# ATWork2022.net
KiCad netlist of a schematic drawn in Altium Designer
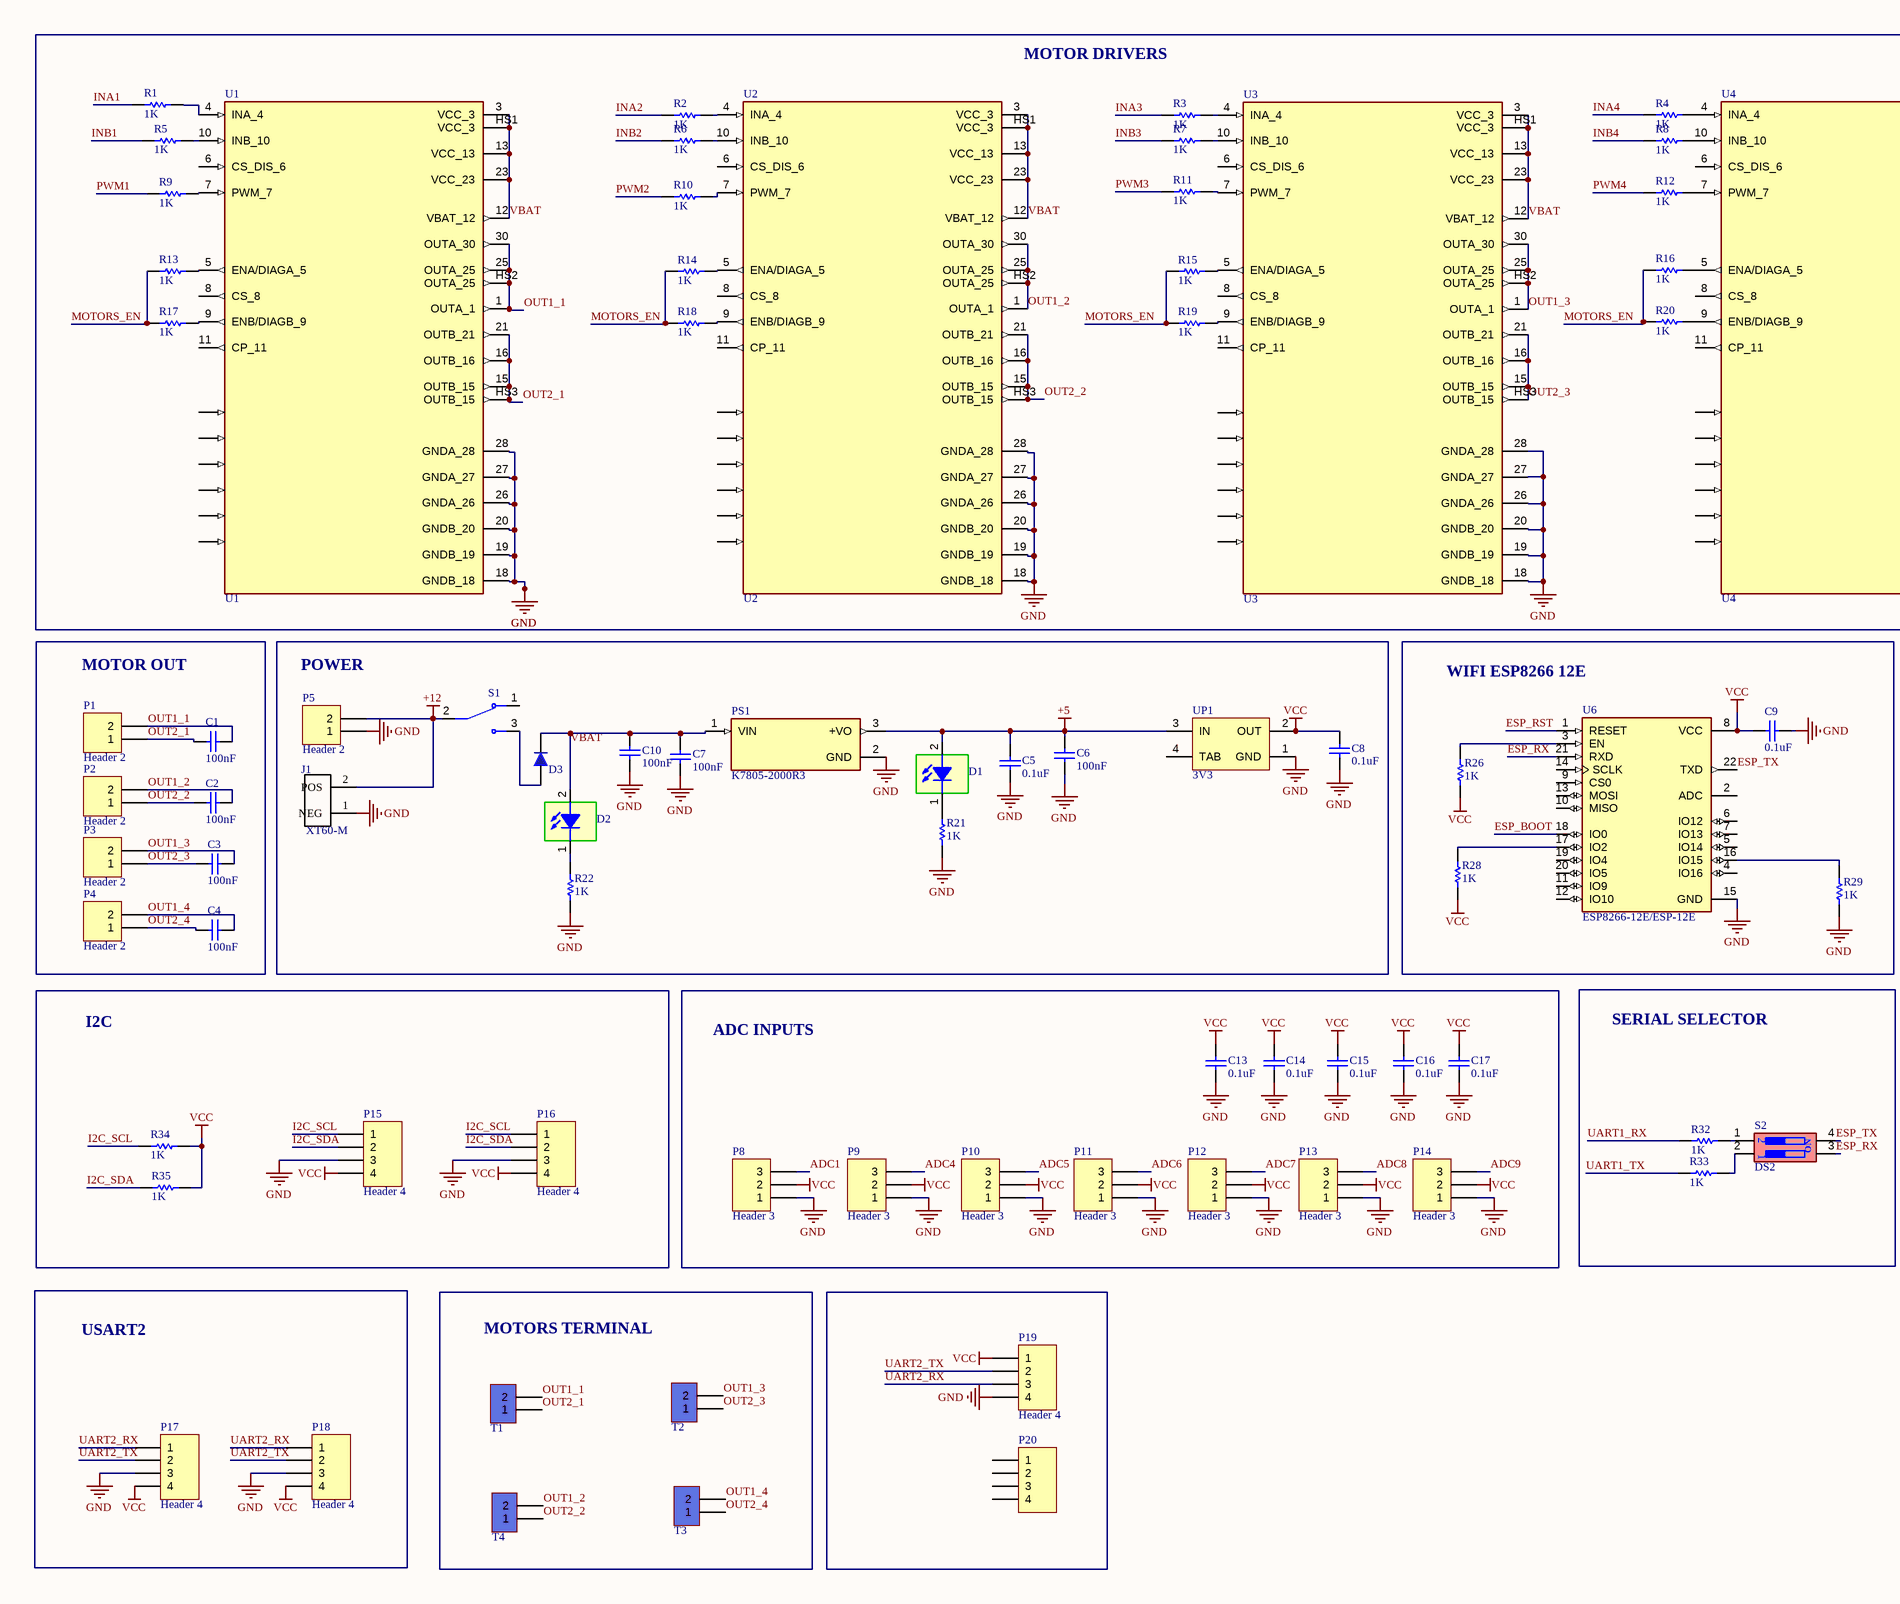
[diagram p0: ATWork2022.SchDoc, left]
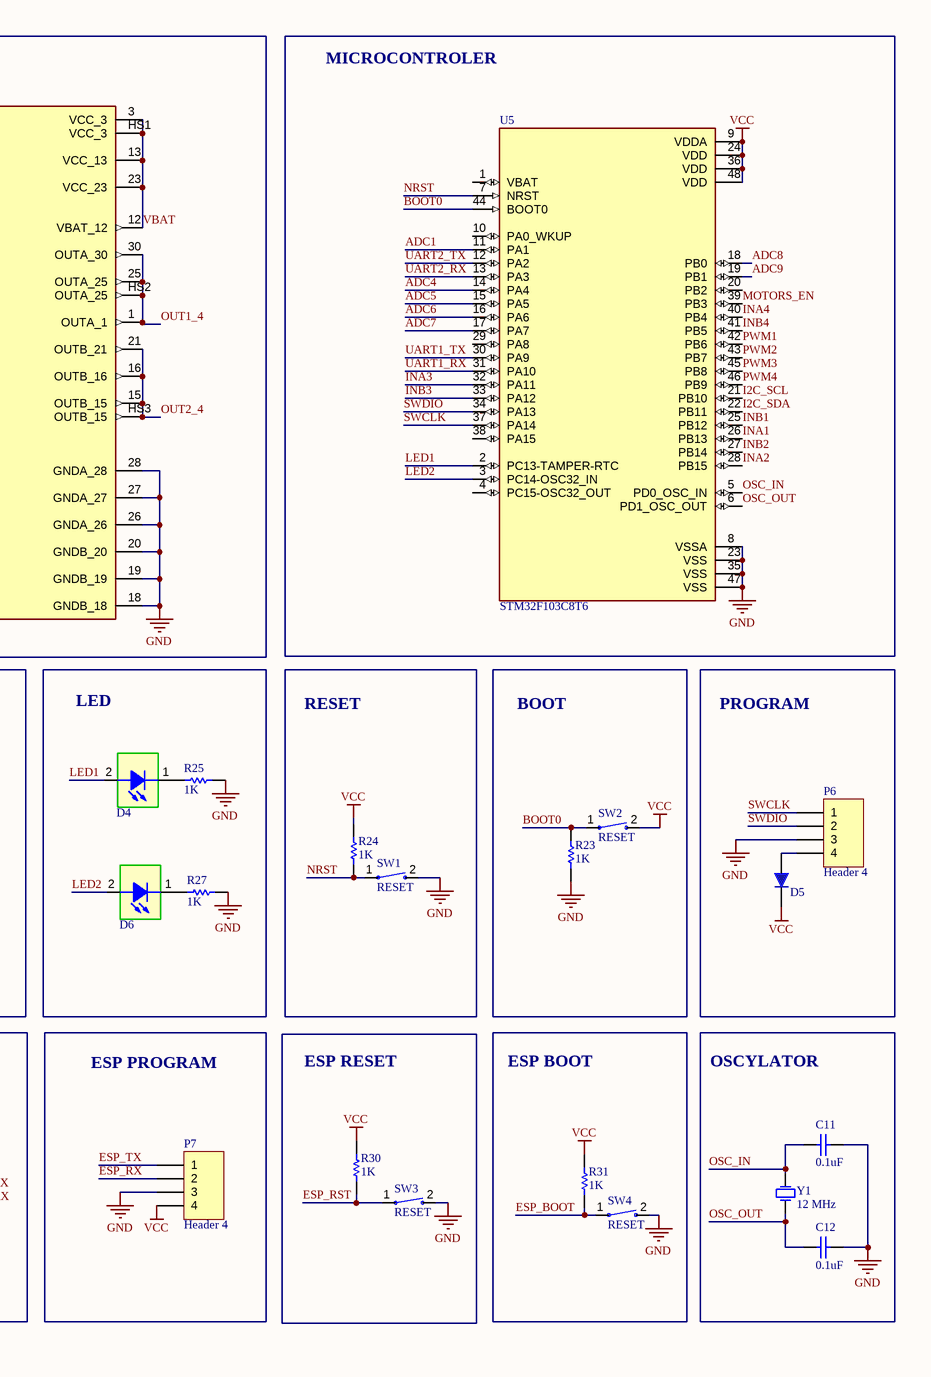
[diagram p1: ATWork2022.SchDoc, right]

(export (version "E")
  (design (tool "Eeschema 10.0.6"))
  (components
    (comp (ref "C1")
      (value "100nF")
      (footprint "CAPC4817X12N")
      (description "CAP 1206")
      (fields (field (name "DESIGNER") "Abbas Basereh"))
      (libsource (lib "Altium") (part "CAP SMD 1206"))
    )
    (comp (ref "C2")
      (value "100nF")
      (footprint "CAPC4817X12N")
      (description "CAP 1206")
      (fields (field (name "DESIGNER") "Abbas Basereh"))
      (libsource (lib "Altium") (part "CAP SMD 1206"))
    )
    (comp (ref "C3")
      (value "100nF")
      (footprint "CAPC4817X12N")
      (description "CAP 1206")
      (fields (field (name "DESIGNER") "Abbas Basereh"))
      (libsource (lib "Altium") (part "CAP SMD 1206"))
    )
    (comp (ref "C4")
      (value "100nF")
      (footprint "CAPC4817X12N")
      (description "CAP 1206")
      (fields (field (name "DESIGNER") "Abbas Basereh"))
      (libsource (lib "Altium") (part "CAP SMD 1206"))
    )
    (comp (ref "C5")
      (value "0.1uF")
      (footprint "CAPC4817X12N")
      (description "CAP 1206")
      (fields (field (name "DESIGNER") "Abbas Basereh"))
      (libsource (lib "Altium") (part "CAP SMD 1206"))
    )
    (comp (ref "C6")
      (value "100nF")
      (footprint "Cap SMD 100UF 35~50v")
      (description "TOTAL CAPACITOR SMD PACK")
      (fields (field (name "DESIGNER") "Abbas Basereh"))
      (libsource (lib "Altium") (part "CAP SMD PACKAGE"))
    )
    (comp (ref "C7")
      (value "100nF")
      (footprint "Cap SMD 100UF 35~50v")
      (description "TOTAL CAPACITOR SMD PACK")
      (fields (field (name "DESIGNER") "Abbas Basereh"))
      (libsource (lib "Altium") (part "CAP SMD PACKAGE"))
    )
    (comp (ref "C8")
      (value "0.1uF")
      (footprint "CAPC4817X12N")
      (description "CAP 1206")
      (fields (field (name "DESIGNER") "Abbas Basereh"))
      (libsource (lib "Altium") (part "CAP SMD 1206"))
    )
    (comp (ref "C9")
      (value "0.1uF")
      (footprint "CAPC4817X12N")
      (description "CAP 1206")
      (fields (field (name "DESIGNER") "Abbas Basereh"))
      (libsource (lib "Altium") (part "CAP SMD 1206"))
    )
    (comp (ref "C10")
      (value "100nF")
      (footprint "Cap SMD 100UF 35~50v")
      (description "TOTAL CAPACITOR SMD PACK")
      (fields (field (name "DESIGNER") "Abbas Basereh"))
      (libsource (lib "Altium") (part "CAP SMD PACKAGE"))
    )
    (comp (ref "C11")
      (value "0.1uF")
      (footprint "CAPC4817X12N")
      (description "CAP 1206")
      (fields (field (name "DESIGNER") "Abbas Basereh"))
      (libsource (lib "Altium") (part "CAP SMD 1206"))
    )
    (comp (ref "C12")
      (value "0.1uF")
      (footprint "CAPC4817X12N")
      (description "CAP 1206")
      (fields (field (name "DESIGNER") "Abbas Basereh"))
      (libsource (lib "Altium") (part "CAP SMD 1206"))
    )
    (comp (ref "C13")
      (value "0.1uF")
      (footprint "CAPC4817X12N")
      (description "CAP 1206")
      (fields (field (name "DESIGNER") "Abbas Basereh"))
      (libsource (lib "Altium") (part "CAP SMD 1206"))
    )
    (comp (ref "C14")
      (value "0.1uF")
      (footprint "CAPC4817X12N")
      (description "CAP 1206")
      (fields (field (name "DESIGNER") "Abbas Basereh"))
      (libsource (lib "Altium") (part "CAP SMD 1206"))
    )
    (comp (ref "C15")
      (value "0.1uF")
      (footprint "CAPC4817X12N")
      (description "CAP 1206")
      (fields (field (name "DESIGNER") "Abbas Basereh"))
      (libsource (lib "Altium") (part "CAP SMD 1206"))
    )
    (comp (ref "C16")
      (value "0.1uF")
      (footprint "CAPC4817X12N")
      (description "CAP 1206")
      (fields (field (name "DESIGNER") "Abbas Basereh"))
      (libsource (lib "Altium") (part "CAP SMD 1206"))
    )
    (comp (ref "C17")
      (value "0.1uF")
      (footprint "CAPC4817X12N")
      (description "CAP 1206")
      (fields (field (name "DESIGNER") "Abbas Basereh"))
      (libsource (lib "Altium") (part "CAP SMD 1206"))
    )
    (comp (ref "D1")
      (value "SMD 1206 LED")
      (footprint "LED 1206")
      (libsource (lib "") (part "LED SMD 1206_1"))
    )
    (comp (ref "D2")
      (value "SMD 1206 LED")
      (footprint "LED 1206")
      (libsource (lib "") (part "LED SMD 1206_1"))
    )
    (comp (ref "D3")
      (value "1n4007")
      (footprint "DIOM4629X24N")
      (description "Standard Rectifiers")
      (fields (field (name "MANUFACTURER") "DC COMPONENTS") (field (name "DESIGNER") "Abbas Basereh"))
      (libsource (lib "Altium") (part "1n4007 SMD M7"))
    )
    (comp (ref "D4")
      (value "SMD 1206 LED")
      (footprint "LED 1206")
      (libsource (lib "Altium") (part "LED SMD 1206"))
    )
    (comp (ref "D5")
      (value "1n4007")
      (footprint "DIOM4629X24N")
      (description "Standard Rectifiers")
      (fields (field (name "MANUFACTURER") "DC COMPONENTS") (field (name "DESIGNER") "Abbas Basereh"))
      (libsource (lib "Altium") (part "1n4007 SMD M7"))
    )
    (comp (ref "D6")
      (value "SMD 1206 LED")
      (footprint "LED 1206")
      (libsource (lib "Altium") (part "LED SMD 1206"))
    )
    (comp (ref "J1")
      (value "XT60-M")
      (footprint "*AMASS_XT60-M")
      (description "Plug; DC supply; XT60; male; PIN: 2; for cable; soldered; 30A; 500V")
      (fields (field (name "MF") "AMASS"))
      (libsource (lib "XT60-M") (part "XT60-M"))
    )
    (comp (ref "P1")
      (value "Header 2")
      (footprint "HDR1X2")
      (description "Header, 2-Pin")
      (fields (field (name "PUBLISHER") "Altium Limited"))
      (libsource (lib "Altium") (part "Header 2"))
    )
    (comp (ref "P2")
      (value "Header 2")
      (footprint "HDR1X2")
      (description "Header, 2-Pin")
      (fields (field (name "PUBLISHER") "Altium Limited"))
      (libsource (lib "Altium") (part "Header 2"))
    )
    (comp (ref "P3")
      (value "Header 2")
      (footprint "HDR1X2")
      (description "Header, 2-Pin")
      (fields (field (name "PUBLISHER") "Altium Limited"))
      (libsource (lib "Altium") (part "Header 2"))
    )
    (comp (ref "P4")
      (value "Header 2")
      (footprint "HDR1X2")
      (description "Header, 2-Pin")
      (fields (field (name "PUBLISHER") "Altium Limited"))
      (libsource (lib "Altium") (part "Header 2"))
    )
    (comp (ref "P5")
      (value "Header 2")
      (footprint "HDR1X2")
      (description "Header, 2-Pin")
      (fields (field (name "PUBLISHER") "Altium Limited"))
      (libsource (lib "Altium") (part "Header 2"))
    )
    (comp (ref "P6")
      (value "Header 4")
      (footprint "HDR1X4")
      (description "Header, 4-Pin")
      (fields (field (name "PUBLISHER") "Altium Limited"))
      (libsource (lib "Altium") (part "Header 4"))
    )
    (comp (ref "P7")
      (value "Header 4")
      (footprint "HDR1X4")
      (description "Header, 4-Pin")
      (fields (field (name "PUBLISHER") "Altium Limited"))
      (libsource (lib "Altium") (part "Header 4"))
    )
    (comp (ref "P8")
      (value "Header 3")
      (footprint "HDR1X3")
      (description "Header, 3-Pin")
      (fields (field (name "PUBLISHER") "Altium Limited"))
      (libsource (lib "Altium") (part "Header 3"))
    )
    (comp (ref "P9")
      (value "Header 3")
      (footprint "HDR1X3")
      (description "Header, 3-Pin")
      (fields (field (name "PUBLISHER") "Altium Limited"))
      (libsource (lib "Altium") (part "Header 3"))
    )
    (comp (ref "P10")
      (value "Header 3")
      (footprint "HDR1X3")
      (description "Header, 3-Pin")
      (fields (field (name "PUBLISHER") "Altium Limited"))
      (libsource (lib "Altium") (part "Header 3"))
    )
    (comp (ref "P11")
      (value "Header 3")
      (footprint "HDR1X3")
      (description "Header, 3-Pin")
      (fields (field (name "PUBLISHER") "Altium Limited"))
      (libsource (lib "Altium") (part "Header 3"))
    )
    (comp (ref "P12")
      (value "Header 3")
      (footprint "HDR1X3")
      (description "Header, 3-Pin")
      (fields (field (name "PUBLISHER") "Altium Limited"))
      (libsource (lib "Altium") (part "Header 3"))
    )
    (comp (ref "P13")
      (value "Header 3")
      (footprint "HDR1X3")
      (description "Header, 3-Pin")
      (fields (field (name "PUBLISHER") "Altium Limited"))
      (libsource (lib "Altium") (part "Header 3"))
    )
    (comp (ref "P14")
      (value "Header 3")
      (footprint "HDR1X3")
      (description "Header, 3-Pin")
      (fields (field (name "PUBLISHER") "Altium Limited"))
      (libsource (lib "Altium") (part "Header 3"))
    )
    (comp (ref "P15")
      (value "Header 4")
      (footprint "HDR1X4")
      (description "Header, 4-Pin")
      (fields (field (name "PUBLISHER") "Altium Limited"))
      (libsource (lib "Altium") (part "Header 4"))
    )
    (comp (ref "P16")
      (value "Header 4")
      (footprint "HDR1X4")
      (description "Header, 4-Pin")
      (fields (field (name "PUBLISHER") "Altium Limited"))
      (libsource (lib "Altium") (part "Header 4"))
    )
    (comp (ref "P17")
      (value "Header 4")
      (footprint "HDR1X4")
      (description "Header, 4-Pin")
      (fields (field (name "PUBLISHER") "Altium Limited"))
      (libsource (lib "Altium") (part "Header 4"))
    )
    (comp (ref "P18")
      (value "Header 4")
      (footprint "HDR1X4")
      (description "Header, 4-Pin")
      (fields (field (name "PUBLISHER") "Altium Limited"))
      (libsource (lib "Altium") (part "Header 4"))
    )
    (comp (ref "P19")
      (value "Header 4")
      (footprint "HDR1X4")
      (description "Header, 4-Pin")
      (fields (field (name "PUBLISHER") "Altium Limited"))
      (libsource (lib "Altium") (part "Header 4"))
    )
    (comp (ref "P20")
      (value "Header 4")
      (footprint "My_1X04")
      (description "Header, 4-Pin")
      (fields (field (name "PUBLISHER") "Altium Limited"))
      (libsource (lib "AMINLIB") (part "Header 4"))
    )
    (comp (ref "PS1")
      (value "K7805-2000R3")
      (footprint "CONV_K7805-2000R3")
      (description "éžçµ¶ç¸åž‹ PoL ãƒ¢ã‚¸ãƒ¥ãƒ¼ãƒ« DC DC ã‚³ãƒ³ãƒãƒ¼ã‚¿ 1 å‡ºåŠ› 5V 2A 8V - 36V å…¥åŠ›")
      (fields
        (field (name "MF") "Mornsun America, LLC")
        (field (name "DIGI-KEY_PART_NUMBER") "2725-K7805-2000R3-ND")
      )
      (libsource (lib "K7805-2000R3") (part "K7805-2000R3"))
    )
    (comp (ref "R1")
      (value "1K")
      (footprint "RESC3413X04N")
      (description "RES 0805")
      (fields (field (name "DESIGNER") "Abbas Basereh"))
      (libsource (lib "Altium") (part "RES 0805 0.125W"))
    )
    (comp (ref "R2")
      (value "1K")
      (footprint "RESC3413X04N")
      (description "RES 0805")
      (fields (field (name "DESIGNER") "Abbas Basereh"))
      (libsource (lib "Altium") (part "RES 0805 0.125W"))
    )
    (comp (ref "R3")
      (value "1K")
      (footprint "RESC3413X04N")
      (description "RES 0805")
      (fields (field (name "DESIGNER") "Abbas Basereh"))
      (libsource (lib "Altium") (part "RES 0805 0.125W"))
    )
    (comp (ref "R4")
      (value "1K")
      (footprint "RESC3413X04N")
      (description "RES 0805")
      (fields (field (name "DESIGNER") "Abbas Basereh"))
      (libsource (lib "Altium") (part "RES 0805 0.125W"))
    )
    (comp (ref "R5")
      (value "1K")
      (footprint "RESC3413X04N")
      (description "RES 0805")
      (fields (field (name "DESIGNER") "Abbas Basereh"))
      (libsource (lib "Altium") (part "RES 0805 0.125W"))
    )
    (comp (ref "R6")
      (value "1K")
      (footprint "RESC3413X04N")
      (description "RES 0805")
      (fields (field (name "DESIGNER") "Abbas Basereh"))
      (libsource (lib "Altium") (part "RES 0805 0.125W"))
    )
    (comp (ref "R7")
      (value "1K")
      (footprint "RESC3413X04N")
      (description "RES 0805")
      (fields (field (name "DESIGNER") "Abbas Basereh"))
      (libsource (lib "Altium") (part "RES 0805 0.125W"))
    )
    (comp (ref "R8")
      (value "1K")
      (footprint "RESC3413X04N")
      (description "RES 0805")
      (fields (field (name "DESIGNER") "Abbas Basereh"))
      (libsource (lib "Altium") (part "RES 0805 0.125W"))
    )
    (comp (ref "R9")
      (value "1K")
      (footprint "RESC3413X04N")
      (description "RES 0805")
      (fields (field (name "DESIGNER") "Abbas Basereh"))
      (libsource (lib "Altium") (part "RES 0805 0.125W"))
    )
    (comp (ref "R10")
      (value "1K")
      (footprint "RESC3413X04N")
      (description "RES 0805")
      (fields (field (name "DESIGNER") "Abbas Basereh"))
      (libsource (lib "Altium") (part "RES 0805 0.125W"))
    )
    (comp (ref "R11")
      (value "1K")
      (footprint "RESC3413X04N")
      (description "RES 0805")
      (fields (field (name "DESIGNER") "Abbas Basereh"))
      (libsource (lib "Altium") (part "RES 0805 0.125W"))
    )
    (comp (ref "R12")
      (value "1K")
      (footprint "RESC3413X04N")
      (description "RES 0805")
      (fields (field (name "DESIGNER") "Abbas Basereh"))
      (libsource (lib "Altium") (part "RES 0805 0.125W"))
    )
    (comp (ref "R13")
      (value "1K")
      (footprint "RESC3413X04N")
      (description "RES 0805")
      (fields (field (name "DESIGNER") "Abbas Basereh"))
      (libsource (lib "Altium") (part "RES 0805 0.125W"))
    )
    (comp (ref "R14")
      (value "1K")
      (footprint "RESC3413X04N")
      (description "RES 0805")
      (fields (field (name "DESIGNER") "Abbas Basereh"))
      (libsource (lib "Altium") (part "RES 0805 0.125W"))
    )
    (comp (ref "R15")
      (value "1K")
      (footprint "RESC3413X04N")
      (description "RES 0805")
      (fields (field (name "DESIGNER") "Abbas Basereh"))
      (libsource (lib "Altium") (part "RES 0805 0.125W"))
    )
    (comp (ref "R16")
      (value "1K")
      (footprint "RESC3413X04N")
      (description "RES 0805")
      (fields (field (name "DESIGNER") "Abbas Basereh"))
      (libsource (lib "Altium") (part "RES 0805 0.125W"))
    )
    (comp (ref "R17")
      (value "1K")
      (footprint "RESC3413X04N")
      (description "RES 0805")
      (fields (field (name "DESIGNER") "Abbas Basereh"))
      (libsource (lib "Altium") (part "RES 0805 0.125W"))
    )
    (comp (ref "R18")
      (value "1K")
      (footprint "RESC3413X04N")
      (description "RES 0805")
      (fields (field (name "DESIGNER") "Abbas Basereh"))
      (libsource (lib "Altium") (part "RES 0805 0.125W"))
    )
    (comp (ref "R19")
      (value "1K")
      (footprint "RESC3413X04N")
      (description "RES 0805")
      (fields (field (name "DESIGNER") "Abbas Basereh"))
      (libsource (lib "Altium") (part "RES 0805 0.125W"))
    )
    (comp (ref "R20")
      (value "1K")
      (footprint "RESC3413X04N")
      (description "RES 0805")
      (fields (field (name "DESIGNER") "Abbas Basereh"))
      (libsource (lib "Altium") (part "RES 0805 0.125W"))
    )
    (comp (ref "R21")
      (value "1K")
      (footprint "RESC3413X04N")
      (description "RES 0805")
      (fields (field (name "DESIGNER") "Abbas Basereh"))
      (libsource (lib "Altium") (part "RES 0805 0.125W"))
    )
    (comp (ref "R22")
      (value "1K")
      (footprint "RESC3413X04N")
      (description "RES 0805")
      (fields (field (name "DESIGNER") "Abbas Basereh"))
      (libsource (lib "Altium") (part "RES 0805 0.125W"))
    )
    (comp (ref "R23")
      (value "1K")
      (footprint "RESC3413X04N")
      (description "RES 0805")
      (fields (field (name "DESIGNER") "Abbas Basereh"))
      (libsource (lib "Altium") (part "RES 0805 0.125W"))
    )
    (comp (ref "R24")
      (value "1K")
      (footprint "RESC3413X04N")
      (description "RES 0805")
      (fields (field (name "DESIGNER") "Abbas Basereh"))
      (libsource (lib "Altium") (part "RES 0805 0.125W"))
    )
    (comp (ref "R25")
      (value "1K")
      (footprint "RESC3413X04N")
      (description "RES 0805")
      (fields (field (name "DESIGNER") "Abbas Basereh"))
      (libsource (lib "Altium") (part "RES 0805 0.125W"))
    )
    (comp (ref "R26")
      (value "1K")
      (footprint "RESC3413X04N")
      (description "RES 0805")
      (fields (field (name "DESIGNER") "Abbas Basereh"))
      (libsource (lib "Altium") (part "RES 0805 0.125W"))
    )
    (comp (ref "R27")
      (value "1K")
      (footprint "RESC3413X04N")
      (description "RES 0805")
      (fields (field (name "DESIGNER") "Abbas Basereh"))
      (libsource (lib "Altium") (part "RES 0805 0.125W"))
    )
    (comp (ref "R28")
      (value "1K")
      (footprint "RESC3413X04N")
      (description "RES 0805")
      (fields (field (name "DESIGNER") "Abbas Basereh"))
      (libsource (lib "Altium") (part "RES 0805 0.125W"))
    )
    (comp (ref "R29")
      (value "1K")
      (footprint "RESC3413X04N")
      (description "RES 0805")
      (fields (field (name "DESIGNER") "Abbas Basereh"))
      (libsource (lib "Altium") (part "RES 0805 0.125W"))
    )
    (comp (ref "R30")
      (value "1K")
      (footprint "RESC3413X04N")
      (description "RES 0805")
      (fields (field (name "DESIGNER") "Abbas Basereh"))
      (libsource (lib "Altium") (part "RES 0805 0.125W"))
    )
    (comp (ref "R31")
      (value "1K")
      (footprint "RESC3413X04N")
      (description "RES 0805")
      (fields (field (name "DESIGNER") "Abbas Basereh"))
      (libsource (lib "Altium") (part "RES 0805 0.125W"))
    )
    (comp (ref "R32")
      (value "1K")
      (footprint "RESC3413X04N")
      (description "RES 0805")
      (fields (field (name "DESIGNER") "Abbas Basereh"))
      (libsource (lib "Altium") (part "RES 0805 0.125W"))
    )
    (comp (ref "R33")
      (value "1K")
      (footprint "RESC3413X04N")
      (description "RES 0805")
      (fields (field (name "DESIGNER") "Abbas Basereh"))
      (libsource (lib "Altium") (part "RES 0805 0.125W"))
    )
    (comp (ref "R34")
      (value "1K")
      (footprint "RESC3413X04N")
      (description "RES 0805")
      (fields (field (name "DESIGNER") "Abbas Basereh"))
      (libsource (lib "Altium") (part "RES 0805 0.125W"))
    )
    (comp (ref "R35")
      (value "1K")
      (footprint "RESC3413X04N")
      (description "RES 0805")
      (fields (field (name "DESIGNER") "Abbas Basereh"))
      (libsource (lib "Altium") (part "RES 0805 0.125W"))
    )
    (comp (ref "S1")
      (value "~")
      (footprint "SW_100SP1T1B4M2QE")
      (description "Toggle Switch SPDT Through Hole")
      (fields (field (name "MP") "100SP1T1B4M2QE"))
      (libsource (lib "100SP1T1B4M2QE") (part "100SP1T1B4M2QE"))
    )
    (comp (ref "S2")
      (value "DS2")
      (footprint "DIP Switch x2")
      (description "2 BIT DIP Switch")
      (libsource (lib "Altium") (part "DIP Switch 2"))
    )
    (comp (ref "SW1")
      (value "RESET")
      (footprint "SW_147873-1")
      (description "Switch Tactile OFF (ON) SPST Rectangular Button J-Bend 0.05A 24VDC 1.77N SMD T/R")
      (fields (field (name "MF") "TE Connectivity") (field (name "MP") "147873-1"))
      (libsource (lib "147873-1") (part "147873-1"))
    )
    (comp (ref "SW2")
      (value "RESET")
      (footprint "SW_147873-1")
      (description "Switch Tactile OFF (ON) SPST Rectangular Button J-Bend 0.05A 24VDC 1.77N SMD T/R")
      (fields (field (name "MF") "TE Connectivity") (field (name "MP") "147873-1"))
      (libsource (lib "147873-1") (part "147873-1"))
    )
    (comp (ref "SW3")
      (value "RESET")
      (footprint "SW_147873-1")
      (description "Switch Tactile OFF (ON) SPST Rectangular Button J-Bend 0.05A 24VDC 1.77N SMD T/R")
      (fields (field (name "MF") "TE Connectivity") (field (name "MP") "147873-1"))
      (libsource (lib "147873-1") (part "147873-1"))
    )
    (comp (ref "SW4")
      (value "RESET")
      (footprint "SW_147873-1")
      (description "Switch Tactile OFF (ON) SPST Rectangular Button J-Bend 0.05A 24VDC 1.77N SMD T/R")
      (fields (field (name "MF") "TE Connectivity") (field (name "MP") "147873-1"))
      (libsource (lib "147873-1") (part "147873-1"))
    )
    (comp (ref "T1")
      (value "KF301_Terminal")
      (footprint "KF301 2PIN")
      (description "Terminal 2 Pin 250VAC 16A")
      (fields (field (name "DESIGNER") "Abbas Basereh"))
      (libsource (lib "Altium") (part "KF301-2Pin_Terminal"))
    )
    (comp (ref "T2")
      (value "KF301_Terminal")
      (footprint "KF301 2PIN")
      (description "Terminal 2 Pin 250VAC 16A")
      (fields (field (name "DESIGNER") "Abbas Basereh"))
      (libsource (lib "Altium") (part "KF301-2Pin_Terminal"))
    )
    (comp (ref "T3")
      (value "KF301_Terminal")
      (footprint "KF301 2PIN")
      (description "Terminal 2 Pin 250VAC 16A")
      (fields (field (name "DESIGNER") "Abbas Basereh"))
      (libsource (lib "Altium") (part "KF301-2Pin_Terminal"))
    )
    (comp (ref "T4")
      (value "KF301_Terminal")
      (footprint "KF301 2PIN")
      (description "Terminal 2 Pin 250VAC 16A")
      (fields (field (name "DESIGNER") "Abbas Basereh"))
      (libsource (lib "Altium") (part "KF301-2Pin_Terminal"))
    )
    (comp (ref "U1")
      (value "U1")
      (footprint "IC_MULTIPOWERSO-30TR")
      (description "Motor Driver Power MOSFET Parallel, PWM MultiPowerSO-30")
      (fields (field (name "MP") "VNH5019A-E") (field (name "MF") "STMicroelectronics"))
      (libsource (lib "VNH5019A-E") (part "VNH5019A-E"))
    )
    (comp (ref "U2")
      (value "U2")
      (footprint "IC_MULTIPOWERSO-30TR")
      (description "Motor Driver Power MOSFET Parallel, PWM MultiPowerSO-30")
      (fields (field (name "MP") "VNH5019A-E") (field (name "MF") "STMicroelectronics"))
      (libsource (lib "VNH5019A-E") (part "VNH5019A-E"))
    )
    (comp (ref "U3")
      (value "U3")
      (footprint "IC_MULTIPOWERSO-30TR")
      (description "Motor Driver Power MOSFET Parallel, PWM MultiPowerSO-30")
      (fields (field (name "MP") "VNH5019A-E") (field (name "MF") "STMicroelectronics"))
      (libsource (lib "VNH5019A-E") (part "VNH5019A-E"))
    )
    (comp (ref "U4")
      (value "U4")
      (footprint "IC_MULTIPOWERSO-30TR")
      (description "Motor Driver Power MOSFET Parallel, PWM MultiPowerSO-30")
      (fields (field (name "MP") "VNH5019A-E") (field (name "MF") "STMicroelectronics"))
      (libsource (lib "VNH5019A-E") (part "VNH5019A-E"))
    )
    (comp (ref "U5")
      (value "STM32F103C8T6")
      (footprint "QFP50P900X900X160-48N")
      (libsource (lib "STM32F103C8T6") (part "STM32F103C8T6"))
    )
    (comp (ref "U6")
      (value "ESP8266-12E/ESP-12E")
      (footprint "XCVR_ESP8266-12E/ESP-12E")
      (description "ESP-12E WiFi Module")
      (libsource (lib "ESP8266-12E_ESP-12E") (part "ESP8266-12E/ESP-12E"))
    )
    (comp (ref "UP1")
      (value "3V3")
      (footprint "SOT223")
      (description "x.x Volt, 800mA Low-Dropout Linear Regulator, 4-pin SOT-223")
      (fields (field (name "DESIGNER") "Ali Hafizi"))
      (libsource (lib "Altium") (part "AMS1117-x.x"))
    )
    (comp (ref "Y1")
      (value "12 MHz")
      (footprint "Crystal SMD")
      (description "XTAL Crystal")
      (fields (field (name "DESIGNER") "ABBAS BASEREH"))
      (libsource (lib "Altium") (part "XTAL"))
    )
  )
  (nets
    (net (code "1") (name "+5") (class "Default")
      (node (ref "C5") (pin "2") (pinfunction "2_2") (pintype "passive"))
      (node (ref "C6") (pin "1") (pinfunction "1_1") (pintype "passive"))
      (node (ref "D1") (pin "2") (pinfunction "2_2") (pintype "passive"))
      (node (ref "PS1") (pin "3") (pinfunction "+VO_3") (pintype "output"))
      (node (ref "UP1") (pin "3") (pinfunction "IN_3") (pintype "power_in"))
    )
    (net (code "2") (name "+12") (class "Default")
      (node (ref "J1") (pin "2") (pinfunction "POS_2") (pintype "passive"))
      (node (ref "P5") (pin "2") (pinfunction "2_2") (pintype "passive"))
      (node (ref "S1") (pin "2") (pinfunction "2_2") (pintype "passive"))
    )
    (net (code "3") (name "/ADC1") (class "Default")
      (node (ref "P8") (pin "3") (pinfunction "3_3") (pintype "passive"))
      (node (ref "U5") (pin "11") (pinfunction "PA1_11") (pintype "bidirectional"))
    )
    (net (code "4") (name "/ADC4") (class "Default")
      (node (ref "P9") (pin "3") (pinfunction "3_3") (pintype "passive"))
      (node (ref "U5") (pin "14") (pinfunction "PA4_14") (pintype "bidirectional"))
    )
    (net (code "5") (name "/ADC5") (class "Default")
      (node (ref "P10") (pin "3") (pinfunction "3_3") (pintype "passive"))
      (node (ref "U5") (pin "15") (pinfunction "PA5_15") (pintype "bidirectional"))
    )
    (net (code "6") (name "/ADC6") (class "Default")
      (node (ref "P11") (pin "3") (pinfunction "3_3") (pintype "passive"))
      (node (ref "U5") (pin "16") (pinfunction "PA6_16") (pintype "bidirectional"))
    )
    (net (code "7") (name "/ADC7") (class "Default")
      (node (ref "P12") (pin "3") (pinfunction "3_3") (pintype "passive"))
      (node (ref "U5") (pin "17") (pinfunction "PA7_17") (pintype "bidirectional"))
    )
    (net (code "8") (name "/ADC8") (class "Default")
      (node (ref "P13") (pin "3") (pinfunction "3_3") (pintype "passive"))
      (node (ref "U5") (pin "18") (pinfunction "PB0_18") (pintype "bidirectional"))
    )
    (net (code "9") (name "/ADC9") (class "Default")
      (node (ref "P14") (pin "3") (pinfunction "3_3") (pintype "passive"))
      (node (ref "U5") (pin "19") (pinfunction "PB1_19") (pintype "bidirectional"))
    )
    (net (code "10") (name "/BOOT0") (class "Default")
      (node (ref "R23") (pin "2") (pinfunction "2_2") (pintype "passive"))
      (node (ref "SW2") (pin "1") (pinfunction "1_1") (pintype "passive"))
      (node (ref "U5") (pin "44") (pinfunction "BOOT0_44") (pintype "input"))
    )
    (net (code "11") (name "/ESP_BOOT") (class "Default")
      (node (ref "R31") (pin "1") (pinfunction "1_1") (pintype "passive"))
      (node (ref "SW4") (pin "1") (pinfunction "1_1") (pintype "passive"))
      (node (ref "U6") (pin "18") (pinfunction "IO0_18") (pintype "bidirectional"))
    )
    (net (code "12") (name "/ESP_RST") (class "Default")
      (node (ref "R30") (pin "1") (pinfunction "1_1") (pintype "passive"))
      (node (ref "SW3") (pin "1") (pinfunction "1_1") (pintype "passive"))
      (node (ref "U6") (pin "1") (pinfunction "RESET_1") (pintype "input"))
    )
    (net (code "13") (name "/ESP_RX") (class "Default")
      (node (ref "P7") (pin "2") (pinfunction "2_2") (pintype "passive"))
      (node (ref "S2") (pin "3") (pinfunction "3_3") (pintype "passive"))
      (node (ref "U6") (pin "21") (pinfunction "RXD_21") (pintype "input"))
    )
    (net (code "14") (name "/ESP_TX") (class "Default")
      (node (ref "P7") (pin "1") (pinfunction "1_1") (pintype "passive"))
      (node (ref "S2") (pin "4") (pinfunction "4_4") (pintype "passive"))
      (node (ref "U6") (pin "22") (pinfunction "TXD_22") (pintype "output"))
    )
    (net (code "15") (name "/I2C_SCL") (class "Default")
      (node (ref "P15") (pin "1") (pinfunction "1_1") (pintype "passive"))
      (node (ref "P16") (pin "1") (pinfunction "1_1") (pintype "passive"))
      (node (ref "R34") (pin "1") (pinfunction "1_1") (pintype "passive"))
      (node (ref "U5") (pin "21") (pinfunction "PB10_21") (pintype "bidirectional"))
    )
    (net (code "16") (name "/I2C_SDA") (class "Default")
      (node (ref "P15") (pin "2") (pinfunction "2_2") (pintype "passive"))
      (node (ref "P16") (pin "2") (pinfunction "2_2") (pintype "passive"))
      (node (ref "R35") (pin "1") (pinfunction "1_1") (pintype "passive"))
      (node (ref "U5") (pin "22") (pinfunction "PB11_22") (pintype "bidirectional"))
    )
    (net (code "17") (name "/INA1") (class "Default")
      (node (ref "R1") (pin "1") (pinfunction "1_1") (pintype "passive"))
      (node (ref "U5") (pin "26") (pinfunction "PB13_26") (pintype "bidirectional"))
    )
    (net (code "18") (name "/INA2") (class "Default")
      (node (ref "R2") (pin "1") (pinfunction "1_1") (pintype "passive"))
      (node (ref "U5") (pin "28") (pinfunction "PB15_28") (pintype "bidirectional"))
    )
    (net (code "19") (name "/INA3") (class "Default")
      (node (ref "R3") (pin "1") (pinfunction "1_1") (pintype "passive"))
      (node (ref "U5") (pin "32") (pinfunction "PA11_32") (pintype "bidirectional"))
    )
    (net (code "20") (name "/INA4") (class "Default")
      (node (ref "R4") (pin "1") (pinfunction "1_1") (pintype "passive"))
      (node (ref "U5") (pin "40") (pinfunction "PB4_40") (pintype "bidirectional"))
    )
    (net (code "21") (name "/INB1") (class "Default")
      (node (ref "R5") (pin "1") (pinfunction "1_1") (pintype "passive"))
      (node (ref "U5") (pin "25") (pinfunction "PB12_25") (pintype "bidirectional"))
    )
    (net (code "22") (name "/INB2") (class "Default")
      (node (ref "R6") (pin "1") (pinfunction "1_1") (pintype "passive"))
      (node (ref "U5") (pin "27") (pinfunction "PB14_27") (pintype "bidirectional"))
    )
    (net (code "23") (name "/INB3") (class "Default")
      (node (ref "R7") (pin "1") (pinfunction "1_1") (pintype "passive"))
      (node (ref "U5") (pin "33") (pinfunction "PA12_33") (pintype "bidirectional"))
    )
    (net (code "24") (name "/INB4") (class "Default")
      (node (ref "R8") (pin "1") (pinfunction "1_1") (pintype "passive"))
      (node (ref "U5") (pin "41") (pinfunction "PB5_41") (pintype "bidirectional"))
    )
    (net (code "25") (name "/LED1") (class "Default")
      (node (ref "D4") (pin "2") (pinfunction "2_2") (pintype "passive"))
      (node (ref "U5") (pin "2") (pinfunction "PC13-TAMPER-RTC_2") (pintype "bidirectional"))
    )
    (net (code "26") (name "/LED2") (class "Default")
      (node (ref "D6") (pin "2") (pinfunction "2_2") (pintype "passive"))
      (node (ref "U5") (pin "3") (pinfunction "PC14-OSC32_IN_3") (pintype "bidirectional"))
    )
    (net (code "27") (name "/MOTORS_EN") (class "Default")
      (node (ref "R13") (pin "1") (pinfunction "1_1") (pintype "passive"))
      (node (ref "R14") (pin "1") (pinfunction "1_1") (pintype "passive"))
      (node (ref "R15") (pin "1") (pinfunction "1_1") (pintype "passive"))
      (node (ref "R16") (pin "1") (pinfunction "1_1") (pintype "passive"))
      (node (ref "R17") (pin "1") (pinfunction "1_1") (pintype "passive"))
      (node (ref "R18") (pin "1") (pinfunction "1_1") (pintype "passive"))
      (node (ref "R19") (pin "1") (pinfunction "1_1") (pintype "passive"))
      (node (ref "R20") (pin "1") (pinfunction "1_1") (pintype "passive"))
      (node (ref "U5") (pin "39") (pinfunction "PB3_39") (pintype "bidirectional"))
    )
    (net (code "28") (name "/NRST") (class "Default")
      (node (ref "R24") (pin "2") (pinfunction "2_2") (pintype "passive"))
      (node (ref "SW1") (pin "1") (pinfunction "1_1") (pintype "passive"))
      (node (ref "U5") (pin "7") (pinfunction "NRST_7") (pintype "input"))
    )
    (net (code "29") (name "/OSC_IN") (class "Default")
      (node (ref "C11") (pin "1") (pinfunction "1_1") (pintype "passive"))
      (node (ref "U5") (pin "5") (pinfunction "PD0_OSC_IN_5") (pintype "bidirectional"))
      (node (ref "Y1") (pin "2") (pinfunction "OSC2_2") (pintype "passive"))
    )
    (net (code "30") (name "/OSC_OUT") (class "Default")
      (node (ref "C12") (pin "1") (pinfunction "1_1") (pintype "passive"))
      (node (ref "U5") (pin "6") (pinfunction "PD1_OSC_OUT_6") (pintype "bidirectional"))
      (node (ref "Y1") (pin "1") (pinfunction "OSC1_1") (pintype "passive"))
    )
    (net (code "31") (name "/OUT1_1") (class "Default")
      (node (ref "C1") (pin "1") (pinfunction "1_1") (pintype "passive"))
      (node (ref "P1") (pin "2") (pinfunction "2_2") (pintype "passive"))
      (node (ref "T1") (pin "2") (pinfunction "2_2") (pintype "passive"))
      (node (ref "U1") (pin "1") (pinfunction "OUTA_1_1") (pintype "output"))
      (node (ref "U1") (pin "25") (pinfunction "OUTA_25_25") (pintype "output"))
      (node (ref "U1") (pin "30") (pinfunction "OUTA_30_30") (pintype "output"))
      (node (ref "U1") (pin "HS2") (pinfunction "OUTA_25_HS2") (pintype "output"))
    )
    (net (code "32") (name "/OUT1_2") (class "Default")
      (node (ref "C2") (pin "1") (pinfunction "1_1") (pintype "passive"))
      (node (ref "P2") (pin "2") (pinfunction "2_2") (pintype "passive"))
      (node (ref "T4") (pin "2") (pinfunction "2_2") (pintype "passive"))
      (node (ref "U2") (pin "1") (pinfunction "OUTA_1_1") (pintype "output"))
      (node (ref "U2") (pin "25") (pinfunction "OUTA_25_25") (pintype "output"))
      (node (ref "U2") (pin "30") (pinfunction "OUTA_30_30") (pintype "output"))
      (node (ref "U2") (pin "HS2") (pinfunction "OUTA_25_HS2") (pintype "output"))
    )
    (net (code "33") (name "/OUT1_3") (class "Default")
      (node (ref "C3") (pin "1") (pinfunction "1_1") (pintype "passive"))
      (node (ref "P3") (pin "2") (pinfunction "2_2") (pintype "passive"))
      (node (ref "T2") (pin "2") (pinfunction "2_2") (pintype "passive"))
      (node (ref "U3") (pin "1") (pinfunction "OUTA_1_1") (pintype "output"))
      (node (ref "U3") (pin "25") (pinfunction "OUTA_25_25") (pintype "output"))
      (node (ref "U3") (pin "30") (pinfunction "OUTA_30_30") (pintype "output"))
      (node (ref "U3") (pin "HS2") (pinfunction "OUTA_25_HS2") (pintype "output"))
    )
    (net (code "34") (name "/OUT1_4") (class "Default")
      (node (ref "C4") (pin "1") (pinfunction "1_1") (pintype "passive"))
      (node (ref "P4") (pin "2") (pinfunction "2_2") (pintype "passive"))
      (node (ref "T3") (pin "2") (pinfunction "2_2") (pintype "passive"))
      (node (ref "U4") (pin "1") (pinfunction "OUTA_1_1") (pintype "output"))
      (node (ref "U4") (pin "25") (pinfunction "OUTA_25_25") (pintype "output"))
      (node (ref "U4") (pin "30") (pinfunction "OUTA_30_30") (pintype "output"))
      (node (ref "U4") (pin "HS2") (pinfunction "OUTA_25_HS2") (pintype "output"))
    )
    (net (code "35") (name "/OUT2_1") (class "Default")
      (node (ref "C1") (pin "2") (pinfunction "2_2") (pintype "passive"))
      (node (ref "P1") (pin "1") (pinfunction "1_1") (pintype "passive"))
      (node (ref "T1") (pin "1") (pinfunction "1_1") (pintype "passive"))
      (node (ref "U1") (pin "15") (pinfunction "OUTB_15_15") (pintype "output"))
      (node (ref "U1") (pin "16") (pinfunction "OUTB_16_16") (pintype "output"))
      (node (ref "U1") (pin "21") (pinfunction "OUTB_21_21") (pintype "output"))
      (node (ref "U1") (pin "HS3") (pinfunction "OUTB_15_HS3") (pintype "output"))
    )
    (net (code "36") (name "/OUT2_2") (class "Default")
      (node (ref "C2") (pin "2") (pinfunction "2_2") (pintype "passive"))
      (node (ref "P2") (pin "1") (pinfunction "1_1") (pintype "passive"))
      (node (ref "T4") (pin "1") (pinfunction "1_1") (pintype "passive"))
      (node (ref "U2") (pin "15") (pinfunction "OUTB_15_15") (pintype "output"))
      (node (ref "U2") (pin "16") (pinfunction "OUTB_16_16") (pintype "output"))
      (node (ref "U2") (pin "21") (pinfunction "OUTB_21_21") (pintype "output"))
      (node (ref "U2") (pin "HS3") (pinfunction "OUTB_15_HS3") (pintype "output"))
    )
    (net (code "37") (name "/OUT2_3") (class "Default")
      (node (ref "C3") (pin "2") (pinfunction "2_2") (pintype "passive"))
      (node (ref "P3") (pin "1") (pinfunction "1_1") (pintype "passive"))
      (node (ref "T2") (pin "1") (pinfunction "1_1") (pintype "passive"))
      (node (ref "U3") (pin "15") (pinfunction "OUTB_15_15") (pintype "output"))
      (node (ref "U3") (pin "16") (pinfunction "OUTB_16_16") (pintype "output"))
      (node (ref "U3") (pin "21") (pinfunction "OUTB_21_21") (pintype "output"))
      (node (ref "U3") (pin "HS3") (pinfunction "OUTB_15_HS3") (pintype "output"))
    )
    (net (code "38") (name "/OUT2_4") (class "Default")
      (node (ref "C4") (pin "2") (pinfunction "2_2") (pintype "passive"))
      (node (ref "P4") (pin "1") (pinfunction "1_1") (pintype "passive"))
      (node (ref "T3") (pin "1") (pinfunction "1_1") (pintype "passive"))
      (node (ref "U4") (pin "15") (pinfunction "OUTB_15_15") (pintype "output"))
      (node (ref "U4") (pin "16") (pinfunction "OUTB_16_16") (pintype "output"))
      (node (ref "U4") (pin "21") (pinfunction "OUTB_21_21") (pintype "output"))
      (node (ref "U4") (pin "HS3") (pinfunction "OUTB_15_HS3") (pintype "output"))
    )
    (net (code "39") (name "/PWM1") (class "Default")
      (node (ref "R9") (pin "1") (pinfunction "1_1") (pintype "passive"))
      (node (ref "U5") (pin "42") (pinfunction "PB6_42") (pintype "bidirectional"))
    )
    (net (code "40") (name "/PWM2") (class "Default")
      (node (ref "R10") (pin "1") (pinfunction "1_1") (pintype "passive"))
      (node (ref "U5") (pin "43") (pinfunction "PB7_43") (pintype "bidirectional"))
    )
    (net (code "41") (name "/PWM3") (class "Default")
      (node (ref "R11") (pin "1") (pinfunction "1_1") (pintype "passive"))
      (node (ref "U5") (pin "45") (pinfunction "PB8_45") (pintype "bidirectional"))
    )
    (net (code "42") (name "/PWM4") (class "Default")
      (node (ref "R12") (pin "1") (pinfunction "1_1") (pintype "passive"))
      (node (ref "U5") (pin "46") (pinfunction "PB9_46") (pintype "bidirectional"))
    )
    (net (code "43") (name "/SWCLK") (class "Default")
      (node (ref "P6") (pin "1") (pinfunction "1_1") (pintype "passive"))
      (node (ref "U5") (pin "37") (pinfunction "PA14_37") (pintype "bidirectional"))
    )
    (net (code "44") (name "/SWDIO") (class "Default")
      (node (ref "P6") (pin "2") (pinfunction "2_2") (pintype "passive"))
      (node (ref "U5") (pin "34") (pinfunction "PA13_34") (pintype "bidirectional"))
    )
    (net (code "45") (name "/UART1_RX") (class "Default")
      (node (ref "R32") (pin "1") (pinfunction "1_1") (pintype "passive"))
      (node (ref "U5") (pin "31") (pinfunction "PA10_31") (pintype "bidirectional"))
    )
    (net (code "46") (name "/UART1_TX") (class "Default")
      (node (ref "R33") (pin "2") (pinfunction "2_2") (pintype "passive"))
      (node (ref "U5") (pin "30") (pinfunction "PA9_30") (pintype "bidirectional"))
    )
    (net (code "47") (name "/UART2_RX") (class "Default")
      (node (ref "P17") (pin "1") (pinfunction "1_1") (pintype "passive"))
      (node (ref "P18") (pin "1") (pinfunction "1_1") (pintype "passive"))
      (node (ref "P19") (pin "3") (pinfunction "3_3") (pintype "passive"))
      (node (ref "U5") (pin "13") (pinfunction "PA3_13") (pintype "bidirectional"))
    )
    (net (code "48") (name "/UART2_TX") (class "Default")
      (node (ref "P17") (pin "2") (pinfunction "2_2") (pintype "passive"))
      (node (ref "P18") (pin "2") (pinfunction "2_2") (pintype "passive"))
      (node (ref "P19") (pin "2") (pinfunction "2_2") (pintype "passive"))
      (node (ref "U5") (pin "12") (pinfunction "PA2_12") (pintype "bidirectional"))
    )
    (net (code "49") (name "/VBAT") (class "Default")
      (node (ref "C10") (pin "1") (pinfunction "1_1") (pintype "passive"))
      (node (ref "C7") (pin "1") (pinfunction "1_1") (pintype "passive"))
      (node (ref "D2") (pin "2") (pinfunction "2_2") (pintype "passive"))
      (node (ref "D3") (pin "2") (pintype "passive"))
      (node (ref "PS1") (pin "1") (pinfunction "VIN_1") (pintype "input"))
      (node (ref "U1") (pin "12") (pinfunction "VBAT_12_12") (pintype "output"))
      (node (ref "U1") (pin "13") (pinfunction "VCC_13_13") (pintype "power_in"))
      (node (ref "U1") (pin "23") (pinfunction "VCC_23_23") (pintype "power_in"))
      (node (ref "U1") (pin "3") (pinfunction "VCC_3_3") (pintype "power_in"))
      (node (ref "U1") (pin "HS1") (pinfunction "VCC_3_HS1") (pintype "power_in"))
      (node (ref "U2") (pin "12") (pinfunction "VBAT_12_12") (pintype "output"))
      (node (ref "U2") (pin "13") (pinfunction "VCC_13_13") (pintype "power_in"))
      (node (ref "U2") (pin "23") (pinfunction "VCC_23_23") (pintype "power_in"))
      (node (ref "U2") (pin "3") (pinfunction "VCC_3_3") (pintype "power_in"))
      (node (ref "U2") (pin "HS1") (pinfunction "VCC_3_HS1") (pintype "power_in"))
      (node (ref "U3") (pin "12") (pinfunction "VBAT_12_12") (pintype "output"))
      (node (ref "U3") (pin "13") (pinfunction "VCC_13_13") (pintype "power_in"))
      (node (ref "U3") (pin "23") (pinfunction "VCC_23_23") (pintype "power_in"))
      (node (ref "U3") (pin "3") (pinfunction "VCC_3_3") (pintype "power_in"))
      (node (ref "U3") (pin "HS1") (pinfunction "VCC_3_HS1") (pintype "power_in"))
      (node (ref "U4") (pin "12") (pinfunction "VBAT_12_12") (pintype "output"))
      (node (ref "U4") (pin "13") (pinfunction "VCC_13_13") (pintype "power_in"))
      (node (ref "U4") (pin "23") (pinfunction "VCC_23_23") (pintype "power_in"))
      (node (ref "U4") (pin "3") (pinfunction "VCC_3_3") (pintype "power_in"))
      (node (ref "U4") (pin "HS1") (pinfunction "VCC_3_HS1") (pintype "power_in"))
    )
    (net (code "50") (name "GND") (class "Default")
      (node (ref "C10") (pin "2") (pinfunction "2_2") (pintype "passive"))
      (node (ref "C11") (pin "2") (pinfunction "2_2") (pintype "passive"))
      (node (ref "C12") (pin "2") (pinfunction "2_2") (pintype "passive"))
      (node (ref "C13") (pin "2") (pinfunction "2_2") (pintype "passive"))
      (node (ref "C14") (pin "2") (pinfunction "2_2") (pintype "passive"))
      (node (ref "C15") (pin "2") (pinfunction "2_2") (pintype "passive"))
      (node (ref "C16") (pin "2") (pinfunction "2_2") (pintype "passive"))
      (node (ref "C17") (pin "2") (pinfunction "2_2") (pintype "passive"))
      (node (ref "C5") (pin "1") (pinfunction "1_1") (pintype "passive"))
      (node (ref "C6") (pin "2") (pinfunction "2_2") (pintype "passive"))
      (node (ref "C7") (pin "2") (pinfunction "2_2") (pintype "passive"))
      (node (ref "C8") (pin "1") (pinfunction "1_1") (pintype "passive"))
      (node (ref "C9") (pin "1") (pinfunction "1_1") (pintype "passive"))
      (node (ref "J1") (pin "1") (pinfunction "NEG_1") (pintype "passive"))
      (node (ref "P10") (pin "1") (pinfunction "1_1") (pintype "passive"))
      (node (ref "P11") (pin "1") (pinfunction "1_1") (pintype "passive"))
      (node (ref "P12") (pin "1") (pinfunction "1_1") (pintype "passive"))
      (node (ref "P13") (pin "1") (pinfunction "1_1") (pintype "passive"))
      (node (ref "P14") (pin "1") (pinfunction "1_1") (pintype "passive"))
      (node (ref "P15") (pin "3") (pinfunction "3_3") (pintype "passive"))
      (node (ref "P16") (pin "3") (pinfunction "3_3") (pintype "passive"))
      (node (ref "P17") (pin "3") (pinfunction "3_3") (pintype "passive"))
      (node (ref "P18") (pin "3") (pinfunction "3_3") (pintype "passive"))
      (node (ref "P19") (pin "4") (pinfunction "4_4") (pintype "passive"))
      (node (ref "P5") (pin "1") (pinfunction "1_1") (pintype "passive"))
      (node (ref "P6") (pin "3") (pinfunction "3_3") (pintype "passive"))
      (node (ref "P7") (pin "3") (pinfunction "3_3") (pintype "passive"))
      (node (ref "P8") (pin "1") (pinfunction "1_1") (pintype "passive"))
      (node (ref "P9") (pin "1") (pinfunction "1_1") (pintype "passive"))
      (node (ref "PS1") (pin "2") (pinfunction "GND_2") (pintype "power_in"))
      (node (ref "R21") (pin "1") (pinfunction "1_1") (pintype "passive"))
      (node (ref "R22") (pin "1") (pinfunction "1_1") (pintype "passive"))
      (node (ref "R23") (pin "1") (pinfunction "1_1") (pintype "passive"))
      (node (ref "R25") (pin "1") (pinfunction "1_1") (pintype "passive"))
      (node (ref "R27") (pin "1") (pinfunction "1_1") (pintype "passive"))
      (node (ref "R29") (pin "1") (pinfunction "1_1") (pintype "passive"))
      (node (ref "SW1") (pin "2") (pinfunction "2_2") (pintype "passive"))
      (node (ref "SW3") (pin "2") (pinfunction "2_2") (pintype "passive"))
      (node (ref "SW4") (pin "2") (pinfunction "2_2") (pintype "passive"))
      (node (ref "U1") (pin "18") (pinfunction "GNDB_18_18") (pintype "power_in"))
      (node (ref "U1") (pin "19") (pinfunction "GNDB_19_19") (pintype "power_in"))
      (node (ref "U1") (pin "20") (pinfunction "GNDB_20_20") (pintype "power_in"))
      (node (ref "U1") (pin "26") (pinfunction "GNDA_26_26") (pintype "power_in"))
      (node (ref "U1") (pin "27") (pinfunction "GNDA_27_27") (pintype "power_in"))
      (node (ref "U1") (pin "28") (pinfunction "GNDA_28_28") (pintype "power_in"))
      (node (ref "U2") (pin "18") (pinfunction "GNDB_18_18") (pintype "power_in"))
      (node (ref "U2") (pin "19") (pinfunction "GNDB_19_19") (pintype "power_in"))
      (node (ref "U2") (pin "20") (pinfunction "GNDB_20_20") (pintype "power_in"))
      (node (ref "U2") (pin "26") (pinfunction "GNDA_26_26") (pintype "power_in"))
      (node (ref "U2") (pin "27") (pinfunction "GNDA_27_27") (pintype "power_in"))
      (node (ref "U2") (pin "28") (pinfunction "GNDA_28_28") (pintype "power_in"))
      (node (ref "U3") (pin "18") (pinfunction "GNDB_18_18") (pintype "power_in"))
      (node (ref "U3") (pin "19") (pinfunction "GNDB_19_19") (pintype "power_in"))
      (node (ref "U3") (pin "20") (pinfunction "GNDB_20_20") (pintype "power_in"))
      (node (ref "U3") (pin "26") (pinfunction "GNDA_26_26") (pintype "power_in"))
      (node (ref "U3") (pin "27") (pinfunction "GNDA_27_27") (pintype "power_in"))
      (node (ref "U3") (pin "28") (pinfunction "GNDA_28_28") (pintype "power_in"))
      (node (ref "U4") (pin "18") (pinfunction "GNDB_18_18") (pintype "power_in"))
      (node (ref "U4") (pin "19") (pinfunction "GNDB_19_19") (pintype "power_in"))
      (node (ref "U4") (pin "20") (pinfunction "GNDB_20_20") (pintype "power_in"))
      (node (ref "U4") (pin "26") (pinfunction "GNDA_26_26") (pintype "power_in"))
      (node (ref "U4") (pin "27") (pinfunction "GNDA_27_27") (pintype "power_in"))
      (node (ref "U4") (pin "28") (pinfunction "GNDA_28_28") (pintype "power_in"))
      (node (ref "U5") (pin "23") (pinfunction "VSS_23") (pintype "power_in"))
      (node (ref "U5") (pin "35") (pinfunction "VSS_35") (pintype "power_in"))
      (node (ref "U5") (pin "47") (pinfunction "VSS_47") (pintype "power_in"))
      (node (ref "U5") (pin "8") (pinfunction "VSSA_8") (pintype "power_in"))
      (node (ref "U6") (pin "15") (pinfunction "GND_15") (pintype "power_in"))
      (node (ref "UP1") (pin "1") (pinfunction "GND_1") (pintype "power_in"))
    )
    (net (code "51") (name "Net-(D1-Pad1)") (class "Default")
      (node (ref "D1") (pin "1") (pinfunction "1_1") (pintype "passive"))
      (node (ref "R21") (pin "2") (pinfunction "2_2") (pintype "passive"))
    )
    (net (code "52") (name "Net-(D2-Pad1)") (class "Default")
      (node (ref "D2") (pin "1") (pinfunction "1_1") (pintype "passive"))
      (node (ref "R22") (pin "2") (pinfunction "2_2") (pintype "passive"))
    )
    (net (code "53") (name "Net-(D3-Pad1)") (class "Default")
      (node (ref "D3") (pin "1") (pintype "passive"))
      (node (ref "S1") (pin "3") (pinfunction "3_3") (pintype "passive"))
    )
    (net (code "54") (name "Net-(D4-Pad1)") (class "Default")
      (node (ref "D4") (pin "1") (pinfunction "1_1") (pintype "passive"))
      (node (ref "R25") (pin "2") (pinfunction "2_2") (pintype "passive"))
    )
    (net (code "55") (name "Net-(D5-Pad1)") (class "Default")
      (node (ref "D5") (pin "1") (pintype "passive"))
      (node (ref "P6") (pin "4") (pinfunction "4_4") (pintype "passive"))
    )
    (net (code "56") (name "Net-(D6-Pad1)") (class "Default")
      (node (ref "D6") (pin "1") (pinfunction "1_1") (pintype "passive"))
      (node (ref "R27") (pin "2") (pinfunction "2_2") (pintype "passive"))
    )
    (net (code "57") (name "Net-(R32-Pad2)") (class "Default")
      (node (ref "R32") (pin "2") (pinfunction "2_2") (pintype "passive"))
      (node (ref "S2") (pin "1") (pinfunction "1_1") (pintype "passive"))
    )
    (net (code "58") (name "Net-(R33-Pad1)") (class "Default")
      (node (ref "R33") (pin "1") (pinfunction "1_1") (pintype "passive"))
      (node (ref "S2") (pin "2") (pinfunction "2_2") (pintype "passive"))
    )
    (net (code "59") (name "Net-(U1-ENA{slash}DIAGA_5)") (class "Default")
      (node (ref "R13") (pin "2") (pinfunction "2_2") (pintype "passive"))
      (node (ref "U1") (pin "5") (pinfunction "ENA/DIAGA_5_5") (pintype "output"))
    )
    (net (code "60") (name "Net-(U1-ENB{slash}DIAGB_9)") (class "Default")
      (node (ref "R17") (pin "2") (pinfunction "2_2") (pintype "passive"))
      (node (ref "U1") (pin "9") (pinfunction "ENB/DIAGB_9_9") (pintype "output"))
    )
    (net (code "61") (name "Net-(U1-INA_4)") (class "Default")
      (node (ref "R1") (pin "2") (pinfunction "2_2") (pintype "passive"))
      (node (ref "U1") (pin "4") (pinfunction "INA_4_4") (pintype "input"))
    )
    (net (code "62") (name "Net-(U1-INB_10)") (class "Default")
      (node (ref "R5") (pin "2") (pinfunction "2_2") (pintype "passive"))
      (node (ref "U1") (pin "10") (pinfunction "INB_10_10") (pintype "input"))
    )
    (net (code "63") (name "Net-(U1-PWM_7)") (class "Default")
      (node (ref "R9") (pin "2") (pinfunction "2_2") (pintype "passive"))
      (node (ref "U1") (pin "7") (pinfunction "PWM_7_7") (pintype "input"))
    )
    (net (code "64") (name "Net-(U2-ENA{slash}DIAGA_5)") (class "Default")
      (node (ref "R14") (pin "2") (pinfunction "2_2") (pintype "passive"))
      (node (ref "U2") (pin "5") (pinfunction "ENA/DIAGA_5_5") (pintype "output"))
    )
    (net (code "65") (name "Net-(U2-ENB{slash}DIAGB_9)") (class "Default")
      (node (ref "R18") (pin "2") (pinfunction "2_2") (pintype "passive"))
      (node (ref "U2") (pin "9") (pinfunction "ENB/DIAGB_9_9") (pintype "output"))
    )
    (net (code "66") (name "Net-(U2-INA_4)") (class "Default")
      (node (ref "R2") (pin "2") (pinfunction "2_2") (pintype "passive"))
      (node (ref "U2") (pin "4") (pinfunction "INA_4_4") (pintype "input"))
    )
    (net (code "67") (name "Net-(U2-INB_10)") (class "Default")
      (node (ref "R6") (pin "2") (pinfunction "2_2") (pintype "passive"))
      (node (ref "U2") (pin "10") (pinfunction "INB_10_10") (pintype "input"))
    )
    (net (code "68") (name "Net-(U2-PWM_7)") (class "Default")
      (node (ref "R10") (pin "2") (pinfunction "2_2") (pintype "passive"))
      (node (ref "U2") (pin "7") (pinfunction "PWM_7_7") (pintype "input"))
    )
    (net (code "69") (name "Net-(U3-ENA{slash}DIAGA_5)") (class "Default")
      (node (ref "R15") (pin "2") (pinfunction "2_2") (pintype "passive"))
      (node (ref "U3") (pin "5") (pinfunction "ENA/DIAGA_5_5") (pintype "output"))
    )
    (net (code "70") (name "Net-(U3-ENB{slash}DIAGB_9)") (class "Default")
      (node (ref "R19") (pin "2") (pinfunction "2_2") (pintype "passive"))
      (node (ref "U3") (pin "9") (pinfunction "ENB/DIAGB_9_9") (pintype "output"))
    )
    (net (code "71") (name "Net-(U3-INA_4)") (class "Default")
      (node (ref "R3") (pin "2") (pinfunction "2_2") (pintype "passive"))
      (node (ref "U3") (pin "4") (pinfunction "INA_4_4") (pintype "input"))
    )
    (net (code "72") (name "Net-(U3-INB_10)") (class "Default")
      (node (ref "R7") (pin "2") (pinfunction "2_2") (pintype "passive"))
      (node (ref "U3") (pin "10") (pinfunction "INB_10_10") (pintype "input"))
    )
    (net (code "73") (name "Net-(U3-PWM_7)") (class "Default")
      (node (ref "R11") (pin "2") (pinfunction "2_2") (pintype "passive"))
      (node (ref "U3") (pin "7") (pinfunction "PWM_7_7") (pintype "input"))
    )
    (net (code "74") (name "Net-(U4-ENA{slash}DIAGA_5)") (class "Default")
      (node (ref "R16") (pin "2") (pinfunction "2_2") (pintype "passive"))
      (node (ref "U4") (pin "5") (pinfunction "ENA/DIAGA_5_5") (pintype "output"))
    )
    (net (code "75") (name "Net-(U4-ENB{slash}DIAGB_9)") (class "Default")
      (node (ref "R20") (pin "2") (pinfunction "2_2") (pintype "passive"))
      (node (ref "U4") (pin "9") (pinfunction "ENB/DIAGB_9_9") (pintype "output"))
    )
    (net (code "76") (name "Net-(U4-INA_4)") (class "Default")
      (node (ref "R4") (pin "2") (pinfunction "2_2") (pintype "passive"))
      (node (ref "U4") (pin "4") (pinfunction "INA_4_4") (pintype "input"))
    )
    (net (code "77") (name "Net-(U4-INB_10)") (class "Default")
      (node (ref "R8") (pin "2") (pinfunction "2_2") (pintype "passive"))
      (node (ref "U4") (pin "10") (pinfunction "INB_10_10") (pintype "input"))
    )
    (net (code "78") (name "Net-(U4-PWM_7)") (class "Default")
      (node (ref "R12") (pin "2") (pinfunction "2_2") (pintype "passive"))
      (node (ref "U4") (pin "7") (pinfunction "PWM_7_7") (pintype "input"))
    )
    (net (code "79") (name "Net-(U6-EN)") (class "Default")
      (node (ref "R26") (pin "1") (pinfunction "1_1") (pintype "passive"))
      (node (ref "U6") (pin "3") (pinfunction "EN_3") (pintype "input"))
    )
    (net (code "80") (name "Net-(U6-IO2)") (class "Default")
      (node (ref "R28") (pin "1") (pinfunction "1_1") (pintype "passive"))
      (node (ref "U6") (pin "17") (pinfunction "IO2_17") (pintype "bidirectional"))
    )
    (net (code "81") (name "Net-(U6-IO15)") (class "Default")
      (node (ref "R29") (pin "2") (pinfunction "2_2") (pintype "passive"))
      (node (ref "U6") (pin "16") (pinfunction "IO15_16") (pintype "bidirectional"))
    )
    (net (code "82") (name "VCC") (class "Default")
      (node (ref "C13") (pin "1") (pinfunction "1_1") (pintype "passive"))
      (node (ref "C14") (pin "1") (pinfunction "1_1") (pintype "passive"))
      (node (ref "C15") (pin "1") (pinfunction "1_1") (pintype "passive"))
      (node (ref "C16") (pin "1") (pinfunction "1_1") (pintype "passive"))
      (node (ref "C17") (pin "1") (pinfunction "1_1") (pintype "passive"))
      (node (ref "C8") (pin "2") (pinfunction "2_2") (pintype "passive"))
      (node (ref "C9") (pin "2") (pinfunction "2_2") (pintype "passive"))
      (node (ref "D5") (pin "2") (pintype "passive"))
      (node (ref "P10") (pin "2") (pinfunction "2_2") (pintype "passive"))
      (node (ref "P11") (pin "2") (pinfunction "2_2") (pintype "passive"))
      (node (ref "P12") (pin "2") (pinfunction "2_2") (pintype "passive"))
      (node (ref "P13") (pin "2") (pinfunction "2_2") (pintype "passive"))
      (node (ref "P14") (pin "2") (pinfunction "2_2") (pintype "passive"))
      (node (ref "P15") (pin "4") (pinfunction "4_4") (pintype "passive"))
      (node (ref "P16") (pin "4") (pinfunction "4_4") (pintype "passive"))
      (node (ref "P17") (pin "4") (pinfunction "4_4") (pintype "passive"))
      (node (ref "P18") (pin "4") (pinfunction "4_4") (pintype "passive"))
      (node (ref "P19") (pin "1") (pinfunction "1_1") (pintype "passive"))
      (node (ref "P7") (pin "4") (pinfunction "4_4") (pintype "passive"))
      (node (ref "P8") (pin "2") (pinfunction "2_2") (pintype "passive"))
      (node (ref "P9") (pin "2") (pinfunction "2_2") (pintype "passive"))
      (node (ref "R24") (pin "1") (pinfunction "1_1") (pintype "passive"))
      (node (ref "R26") (pin "2") (pinfunction "2_2") (pintype "passive"))
      (node (ref "R28") (pin "2") (pinfunction "2_2") (pintype "passive"))
      (node (ref "R30") (pin "2") (pinfunction "2_2") (pintype "passive"))
      (node (ref "R31") (pin "2") (pinfunction "2_2") (pintype "passive"))
      (node (ref "R34") (pin "2") (pinfunction "2_2") (pintype "passive"))
      (node (ref "R35") (pin "2") (pinfunction "2_2") (pintype "passive"))
      (node (ref "SW2") (pin "2") (pinfunction "2_2") (pintype "passive"))
      (node (ref "U5") (pin "24") (pinfunction "VDD_24") (pintype "power_in"))
      (node (ref "U5") (pin "36") (pinfunction "VDD_36") (pintype "power_in"))
      (node (ref "U5") (pin "48") (pinfunction "VDD_48") (pintype "power_in"))
      (node (ref "U5") (pin "9") (pinfunction "VDDA_9") (pintype "power_in"))
      (node (ref "U6") (pin "8") (pinfunction "VCC_8") (pintype "power_in"))
      (node (ref "UP1") (pin "2") (pinfunction "OUT_2") (pintype "power_in"))
    )
    (net (code "83") (name "unconnected-(P20-Pad1)") (class "Default")
      (node (ref "P20") (pin "1") (pinfunction "1_1") (pintype "passive"))
    )
    (net (code "84") (name "unconnected-(P20-Pad2)") (class "Default")
      (node (ref "P20") (pin "2") (pinfunction "2_2") (pintype "passive"))
    )
    (net (code "85") (name "unconnected-(P20-Pad3)") (class "Default")
      (node (ref "P20") (pin "3") (pinfunction "3_3") (pintype "passive"))
    )
    (net (code "86") (name "unconnected-(P20-Pad4)") (class "Default")
      (node (ref "P20") (pin "4") (pinfunction "4_4") (pintype "passive"))
    )
    (net (code "87") (name "unconnected-(S1-Pad1)") (class "Default")
      (node (ref "S1") (pin "1") (pinfunction "1_1") (pintype "passive"))
    )
    (net (code "88") (name "unconnected-(U1-CP_11-Pad11)") (class "Default")
      (node (ref "U1") (pin "11") (pinfunction "CP_11_11") (pintype "output"))
    )
    (net (code "89") (name "unconnected-(U1-CS_8-Pad8)") (class "Default")
      (node (ref "U1") (pin "8") (pinfunction "CS_8_8") (pintype "output"))
    )
    (net (code "90") (name "unconnected-(U1-CS_DIS_6-Pad6)") (class "Default")
      (node (ref "U1") (pin "6") (pinfunction "CS_DIS_6_6") (pintype "input"))
    )
    (net (code "91") (name "unconnected-(U1-N.C._2-Pad2)") (class "Default")
      (node (ref "U1") (pin "2") (pinfunction "N.C._2_2") (pintype "input"))
    )
    (net (code "92") (name "unconnected-(U1-N.C._29-Pad29)") (class "Default")
      (node (ref "U1") (pin "29") (pinfunction "N.C._29_29") (pintype "input"))
    )
    (net (code "93") (name "unconnected-(U1-NC_14-Pad14)") (class "Default")
      (node (ref "U1") (pin "14") (pinfunction "NC_14_14") (pintype "input"))
    )
    (net (code "94") (name "unconnected-(U1-NC_17-Pad17)") (class "Default")
      (node (ref "U1") (pin "17") (pinfunction "NC_17_17") (pintype "input"))
    )
    (net (code "95") (name "unconnected-(U1-NC_22-Pad22)") (class "Default")
      (node (ref "U1") (pin "22") (pinfunction "NC_22_22") (pintype "input"))
    )
    (net (code "96") (name "unconnected-(U1-NC_24-Pad24)") (class "Default")
      (node (ref "U1") (pin "24") (pinfunction "NC_24_24") (pintype "input"))
    )
    (net (code "97") (name "unconnected-(U2-CP_11-Pad11)") (class "Default")
      (node (ref "U2") (pin "11") (pinfunction "CP_11_11") (pintype "output"))
    )
    (net (code "98") (name "unconnected-(U2-CS_8-Pad8)") (class "Default")
      (node (ref "U2") (pin "8") (pinfunction "CS_8_8") (pintype "output"))
    )
    (net (code "99") (name "unconnected-(U2-CS_DIS_6-Pad6)") (class "Default")
      (node (ref "U2") (pin "6") (pinfunction "CS_DIS_6_6") (pintype "input"))
    )
    (net (code "100") (name "unconnected-(U2-N.C._2-Pad2)") (class "Default")
      (node (ref "U2") (pin "2") (pinfunction "N.C._2_2") (pintype "input"))
    )
    (net (code "101") (name "unconnected-(U2-N.C._29-Pad29)") (class "Default")
      (node (ref "U2") (pin "29") (pinfunction "N.C._29_29") (pintype "input"))
    )
    (net (code "102") (name "unconnected-(U2-NC_14-Pad14)") (class "Default")
      (node (ref "U2") (pin "14") (pinfunction "NC_14_14") (pintype "input"))
    )
    (net (code "103") (name "unconnected-(U2-NC_17-Pad17)") (class "Default")
      (node (ref "U2") (pin "17") (pinfunction "NC_17_17") (pintype "input"))
    )
    (net (code "104") (name "unconnected-(U2-NC_22-Pad22)") (class "Default")
      (node (ref "U2") (pin "22") (pinfunction "NC_22_22") (pintype "input"))
    )
    (net (code "105") (name "unconnected-(U2-NC_24-Pad24)") (class "Default")
      (node (ref "U2") (pin "24") (pinfunction "NC_24_24") (pintype "input"))
    )
    (net (code "106") (name "unconnected-(U3-CP_11-Pad11)") (class "Default")
      (node (ref "U3") (pin "11") (pinfunction "CP_11_11") (pintype "output"))
    )
    (net (code "107") (name "unconnected-(U3-CS_8-Pad8)") (class "Default")
      (node (ref "U3") (pin "8") (pinfunction "CS_8_8") (pintype "output"))
    )
    (net (code "108") (name "unconnected-(U3-CS_DIS_6-Pad6)") (class "Default")
      (node (ref "U3") (pin "6") (pinfunction "CS_DIS_6_6") (pintype "input"))
    )
    (net (code "109") (name "unconnected-(U3-N.C._2-Pad2)") (class "Default")
      (node (ref "U3") (pin "2") (pinfunction "N.C._2_2") (pintype "input"))
    )
    (net (code "110") (name "unconnected-(U3-N.C._29-Pad29)") (class "Default")
      (node (ref "U3") (pin "29") (pinfunction "N.C._29_29") (pintype "input"))
    )
    (net (code "111") (name "unconnected-(U3-NC_14-Pad14)") (class "Default")
      (node (ref "U3") (pin "14") (pinfunction "NC_14_14") (pintype "input"))
    )
    (net (code "112") (name "unconnected-(U3-NC_17-Pad17)") (class "Default")
      (node (ref "U3") (pin "17") (pinfunction "NC_17_17") (pintype "input"))
    )
    (net (code "113") (name "unconnected-(U3-NC_22-Pad22)") (class "Default")
      (node (ref "U3") (pin "22") (pinfunction "NC_22_22") (pintype "input"))
    )
    (net (code "114") (name "unconnected-(U3-NC_24-Pad24)") (class "Default")
      (node (ref "U3") (pin "24") (pinfunction "NC_24_24") (pintype "input"))
    )
    (net (code "115") (name "unconnected-(U4-CP_11-Pad11)") (class "Default")
      (node (ref "U4") (pin "11") (pinfunction "CP_11_11") (pintype "output"))
    )
    (net (code "116") (name "unconnected-(U4-CS_8-Pad8)") (class "Default")
      (node (ref "U4") (pin "8") (pinfunction "CS_8_8") (pintype "output"))
    )
    (net (code "117") (name "unconnected-(U4-CS_DIS_6-Pad6)") (class "Default")
      (node (ref "U4") (pin "6") (pinfunction "CS_DIS_6_6") (pintype "input"))
    )
    (net (code "118") (name "unconnected-(U4-N.C._2-Pad2)") (class "Default")
      (node (ref "U4") (pin "2") (pinfunction "N.C._2_2") (pintype "input"))
    )
    (net (code "119") (name "unconnected-(U4-N.C._29-Pad29)") (class "Default")
      (node (ref "U4") (pin "29") (pinfunction "N.C._29_29") (pintype "input"))
    )
    (net (code "120") (name "unconnected-(U4-NC_14-Pad14)") (class "Default")
      (node (ref "U4") (pin "14") (pinfunction "NC_14_14") (pintype "input"))
    )
    (net (code "121") (name "unconnected-(U4-NC_17-Pad17)") (class "Default")
      (node (ref "U4") (pin "17") (pinfunction "NC_17_17") (pintype "input"))
    )
    (net (code "122") (name "unconnected-(U4-NC_22-Pad22)") (class "Default")
      (node (ref "U4") (pin "22") (pinfunction "NC_22_22") (pintype "input"))
    )
    (net (code "123") (name "unconnected-(U4-NC_24-Pad24)") (class "Default")
      (node (ref "U4") (pin "24") (pinfunction "NC_24_24") (pintype "input"))
    )
    (net (code "124") (name "unconnected-(U5-PA0_WKUP-Pad10)") (class "Default")
      (node (ref "U5") (pin "10") (pinfunction "PA0_WKUP_10") (pintype "bidirectional"))
    )
    (net (code "125") (name "unconnected-(U5-PA8-Pad29)") (class "Default")
      (node (ref "U5") (pin "29") (pinfunction "PA8_29") (pintype "bidirectional"))
    )
    (net (code "126") (name "unconnected-(U5-PA15-Pad38)") (class "Default")
      (node (ref "U5") (pin "38") (pinfunction "PA15_38") (pintype "bidirectional"))
    )
    (net (code "127") (name "unconnected-(U5-PB2-Pad20)") (class "Default")
      (node (ref "U5") (pin "20") (pinfunction "PB2_20") (pintype "bidirectional"))
    )
    (net (code "128") (name "unconnected-(U5-PC15-OSC32_OUT-Pad4)") (class "Default")
      (node (ref "U5") (pin "4") (pinfunction "PC15-OSC32_OUT_4") (pintype "bidirectional"))
    )
    (net (code "129") (name "unconnected-(U5-VBAT-Pad1)") (class "Default")
      (node (ref "U5") (pin "1") (pinfunction "VBAT_1") (pintype "bidirectional"))
    )
    (net (code "130") (name "unconnected-(U6-ADC-Pad2)") (class "Default")
      (node (ref "U6") (pin "2") (pinfunction "ADC_2") (pintype "passive"))
    )
    (net (code "131") (name "unconnected-(U6-CS0-Pad9)") (class "Default")
      (node (ref "U6") (pin "9") (pinfunction "CS0_9") (pintype "input"))
    )
    (net (code "132") (name "unconnected-(U6-IO4-Pad19)") (class "Default")
      (node (ref "U6") (pin "19") (pinfunction "IO4_19") (pintype "bidirectional"))
    )
    (net (code "133") (name "unconnected-(U6-IO5-Pad20)") (class "Default")
      (node (ref "U6") (pin "20") (pinfunction "IO5_20") (pintype "bidirectional"))
    )
    (net (code "134") (name "unconnected-(U6-IO9-Pad11)") (class "Default")
      (node (ref "U6") (pin "11") (pinfunction "IO9_11") (pintype "bidirectional"))
    )
    (net (code "135") (name "unconnected-(U6-IO10-Pad12)") (class "Default")
      (node (ref "U6") (pin "12") (pinfunction "IO10_12") (pintype "bidirectional"))
    )
    (net (code "136") (name "unconnected-(U6-IO12-Pad6)") (class "Default")
      (node (ref "U6") (pin "6") (pinfunction "IO12_6") (pintype "bidirectional"))
    )
    (net (code "137") (name "unconnected-(U6-IO13-Pad7)") (class "Default")
      (node (ref "U6") (pin "7") (pinfunction "IO13_7") (pintype "bidirectional"))
    )
    (net (code "138") (name "unconnected-(U6-IO14-Pad5)") (class "Default")
      (node (ref "U6") (pin "5") (pinfunction "IO14_5") (pintype "bidirectional"))
    )
    (net (code "139") (name "unconnected-(U6-IO16-Pad4)") (class "Default")
      (node (ref "U6") (pin "4") (pinfunction "IO16_4") (pintype "bidirectional"))
    )
    (net (code "140") (name "unconnected-(U6-MISO-Pad10)") (class "Default")
      (node (ref "U6") (pin "10") (pinfunction "MISO_10") (pintype "bidirectional"))
    )
    (net (code "141") (name "unconnected-(U6-MOSI-Pad13)") (class "Default")
      (node (ref "U6") (pin "13") (pinfunction "MOSI_13") (pintype "bidirectional"))
    )
    (net (code "142") (name "unconnected-(U6-SCLK-Pad14)") (class "Default")
      (node (ref "U6") (pin "14") (pinfunction "SCLK_14") (pintype "input"))
    )
    (net (code "143") (name "unconnected-(UP1-TAB-Pad4)") (class "Default")
      (node (ref "UP1") (pin "4") (pinfunction "TAB_4") (pintype "power_in"))
    )
  )
)
